# XBee.net
KiCad netlist of a schematic drawn in Altium Designer
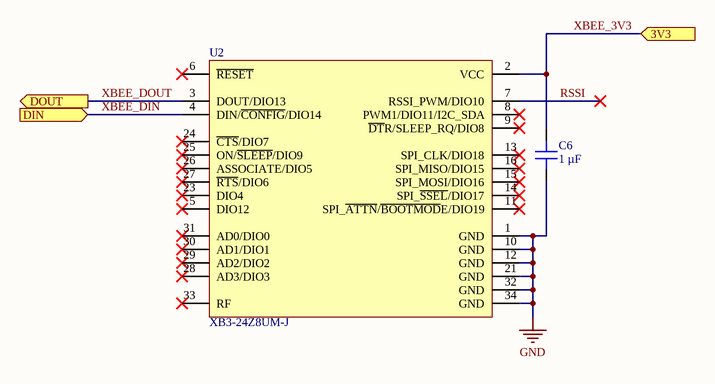
[diagram p0: XBee.SchDoc]

(export (version "E")
  (design (tool "Eeschema 10.0.6"))
  (components
    (comp (ref "C6")
      (value "1 µF")
      (footprint "CAP 0402_1005")
      (description "CAP CER 0.1UF 16V X7R 0402")
      (fields (field (name "PART NUMBER") "C0402C104K4RACAUTO") (field (name "MANUFACTURER") "KEMET"))
      (libsource (lib "Celestial Altium Library - altium_library") (part "Capacitor"))
    )
    (comp (ref "U2")
      (value "XB3-24Z8UM-J")
      (footprint "XCVR_XB3-24Z8UM-J")
      (description "802.15.4 Zigbee Transceiver Module 2.4GHz Antenna Not Included, U.FL Surface Mount")
      (fields (field (name "MF") "Digi International"))
      (libsource (lib "IC") (part "XB3-24Z8UM-J"))
    )
  )
  (nets
    (net (code "1") (name "/RSSI") (class "Default")
      (node (ref "U2") (pin "7") (pinfunction "RSSI_PWM/DIO10_7") (pintype "passive+no_connect"))
    )
    (net (code "2") (name "/XBEE_3V3") (class "Default")
      (node (ref "C6") (pin "1") (pinfunction "1_1") (pintype "passive"))
      (node (ref "U2") (pin "2") (pinfunction "VCC_2") (pintype "passive"))
    )
    (net (code "3") (name "/XBEE_DIN") (class "Default")
      (node (ref "U2") (pin "4") (pinfunction "DIN/~{CONFIG}/DIO14_4") (pintype "passive"))
    )
    (net (code "4") (name "/XBEE_DOUT") (class "Default")
      (node (ref "U2") (pin "3") (pinfunction "DOUT/DIO13_3") (pintype "passive"))
    )
    (net (code "5") (name "GND") (class "Default")
      (node (ref "C6") (pin "2") (pinfunction "2_2") (pintype "passive"))
      (node (ref "U2") (pin "1") (pinfunction "GND_1") (pintype "passive"))
      (node (ref "U2") (pin "10") (pinfunction "GND_10") (pintype "passive"))
      (node (ref "U2") (pin "12") (pinfunction "GND_12") (pintype "passive"))
      (node (ref "U2") (pin "21") (pinfunction "GND_21") (pintype "passive"))
      (node (ref "U2") (pin "32") (pinfunction "GND_32") (pintype "passive"))
      (node (ref "U2") (pin "34") (pinfunction "GND_34") (pintype "passive"))
    )
    (net (code "6") (name "unconnected-(U2-AD0{slash}DIO0-Pad31)") (class "Default")
      (node (ref "U2") (pin "31") (pinfunction "AD0/DIO0_31") (pintype "passive+no_connect"))
    )
    (net (code "7") (name "unconnected-(U2-AD1{slash}DIO1-Pad30)") (class "Default")
      (node (ref "U2") (pin "30") (pinfunction "AD1/DIO1_30") (pintype "passive+no_connect"))
    )
    (net (code "8") (name "unconnected-(U2-AD2{slash}DIO2-Pad29)") (class "Default")
      (node (ref "U2") (pin "29") (pinfunction "AD2/DIO2_29") (pintype "passive+no_connect"))
    )
    (net (code "9") (name "unconnected-(U2-AD3{slash}DIO3-Pad28)") (class "Default")
      (node (ref "U2") (pin "28") (pinfunction "AD3/DIO3_28") (pintype "passive+no_connect"))
    )
    (net (code "10") (name "unconnected-(U2-ASSOCIATE{slash}DIO5-Pad26)") (class "Default")
      (node (ref "U2") (pin "26") (pinfunction "ASSOCIATE/DIO5_26") (pintype "passive+no_connect"))
    )
    (net (code "11") (name "unconnected-(U2-DIO4-Pad23)") (class "Default")
      (node (ref "U2") (pin "23") (pinfunction "DIO4_23") (pintype "passive+no_connect"))
    )
    (net (code "12") (name "unconnected-(U2-DIO12-Pad5)") (class "Default")
      (node (ref "U2") (pin "5") (pinfunction "DIO12_5") (pintype "passive+no_connect"))
    )
    (net (code "13") (name "unconnected-(U2-ON{slash}~{SLEEP}{slash}DIO9-Pad25)") (class "Default")
      (node (ref "U2") (pin "25") (pinfunction "ON/~{SLEEP}/DIO9_25") (pintype "passive+no_connect"))
    )
    (net (code "14") (name "unconnected-(U2-PWM1{slash}DIO11{slash}I2C_SDA-Pad8)") (class "Default")
      (node (ref "U2") (pin "8") (pinfunction "PWM1/DIO11/I2C_SDA_8") (pintype "passive+no_connect"))
    )
    (net (code "15") (name "unconnected-(U2-RF-Pad33)") (class "Default")
      (node (ref "U2") (pin "33") (pinfunction "RF_33") (pintype "passive+no_connect"))
    )
    (net (code "16") (name "unconnected-(U2-SPI_CLK{slash}DIO18-Pad13)") (class "Default")
      (node (ref "U2") (pin "13") (pinfunction "SPI_CLK/DIO18_13") (pintype "passive+no_connect"))
    )
    (net (code "17") (name "unconnected-(U2-SPI_MISO{slash}DIO15-Pad16)") (class "Default")
      (node (ref "U2") (pin "16") (pinfunction "SPI_MISO/DIO15_16") (pintype "passive+no_connect"))
    )
    (net (code "18") (name "unconnected-(U2-SPI_MOSI{slash}DIO16-Pad15)") (class "Default")
      (node (ref "U2") (pin "15") (pinfunction "SPI_MOSI/DIO16_15") (pintype "passive+no_connect"))
    )
    (net (code "19") (name "unconnected-(U2-SPI_~{ATTN}{slash}~{BOOTMOD}E{slash}DIO19-Pad11)") (class "Default")
      (node (ref "U2") (pin "11") (pinfunction "SPI_~{ATTN}/~{BOOTMOD}E/DIO19_11") (pintype "passive+no_connect"))
    )
    (net (code "20") (name "unconnected-(U2-SPI_~{SSEL}{slash}DIO17-Pad14)") (class "Default")
      (node (ref "U2") (pin "14") (pinfunction "SPI_~{SSEL}/DIO17_14") (pintype "passive+no_connect"))
    )
    (net (code "21") (name "unconnected-(U2-~{CTS}{slash}DIO7-Pad24)") (class "Default")
      (node (ref "U2") (pin "24") (pinfunction "~{CTS}/DIO7_24") (pintype "passive+no_connect"))
    )
    (net (code "22") (name "unconnected-(U2-~{DT}R{slash}SLEEP_RQ{slash}DIO8-Pad9)") (class "Default")
      (node (ref "U2") (pin "9") (pinfunction "~{DT}R/SLEEP_RQ/DIO8_9") (pintype "passive+no_connect"))
    )
    (net (code "23") (name "unconnected-(U2-~{RESET}-Pad6)") (class "Default")
      (node (ref "U2") (pin "6") (pinfunction "~{RESET}_6") (pintype "passive+no_connect"))
    )
    (net (code "24") (name "unconnected-(U2-~{RTS}{slash}DIO6-Pad27)") (class "Default")
      (node (ref "U2") (pin "27") (pinfunction "~{RTS}/DIO6_27") (pintype "passive+no_connect"))
    )
  )
)
